# RelayBypass.net
KiCad netlist of a schematic drawn in Altium Designer
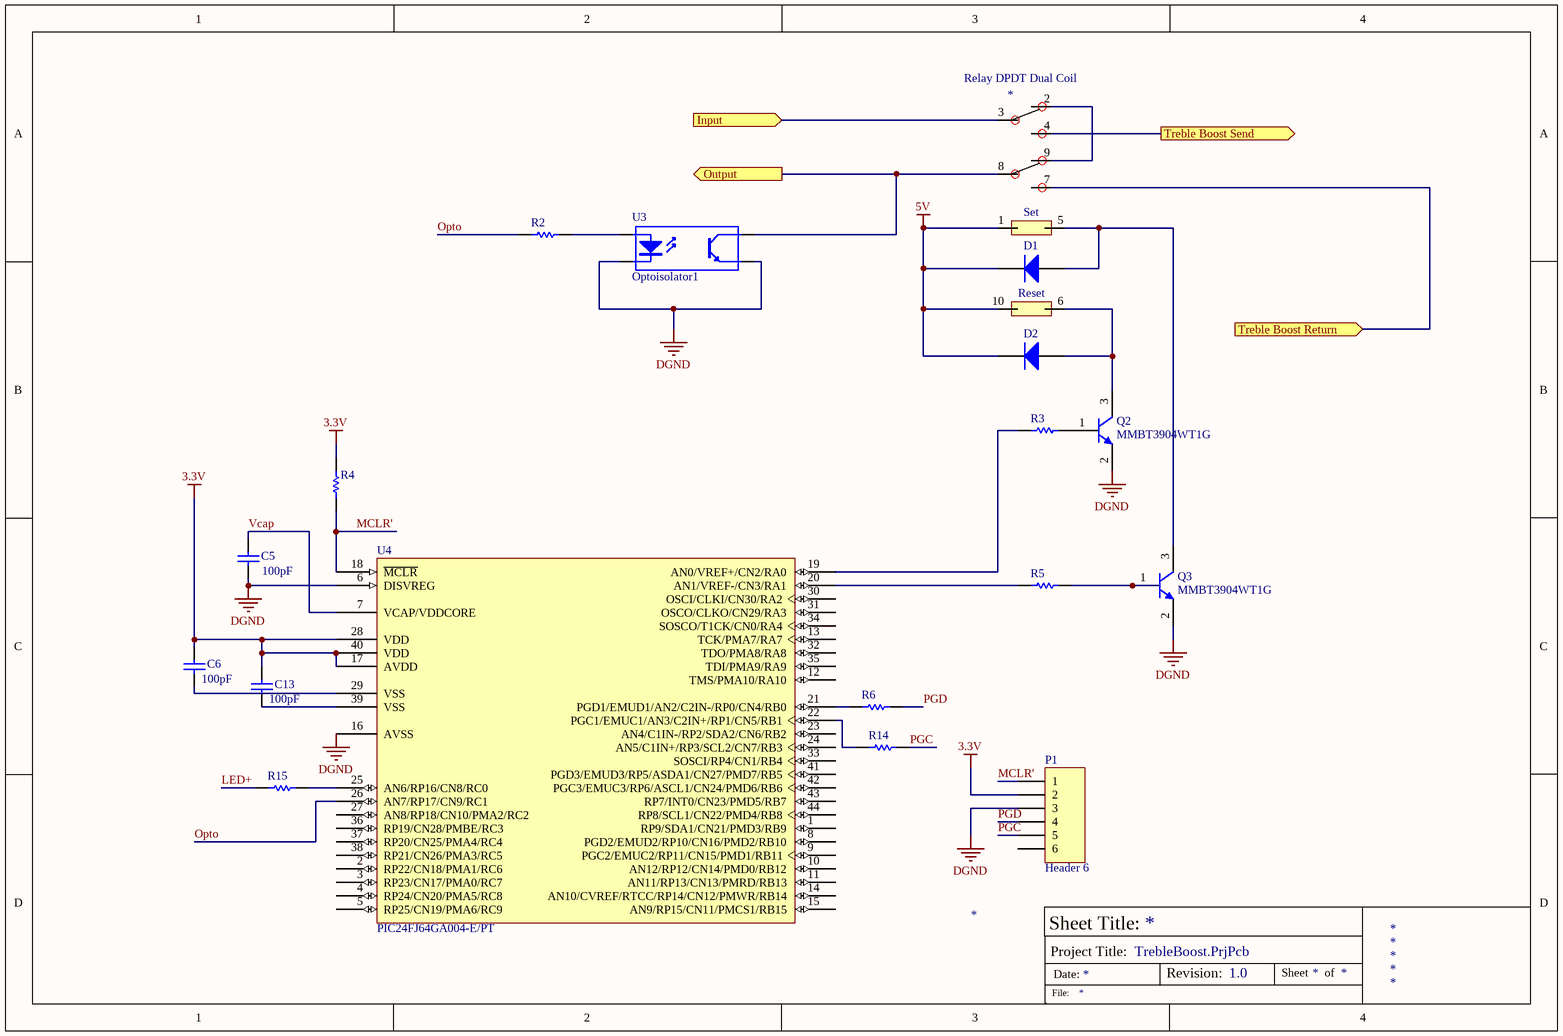
[diagram p0: RelayBypass.SchDoc]

(export (version "E")
  (design (tool "Eeschema 10.0.6"))
  (components
    (comp (ref "*")
      (value "Relay DPDT Dual Coil")
      (footprint "EB2 Relay")
      (libsource (lib "Parts") (part "Relay DPDT Dual Coil"))
    )
    (comp (ref "C5")
      (value "100pF")
      (footprint "1210")
      (description "Ceramic Chip Capacitor - Standard")
      (fields (field (name "Comment") "C1210") (field (name "PUBLISHER") "Altium Limited"))
      (libsource (lib "KEMET Chip Capacitor") (part "C1210"))
    )
    (comp (ref "C6")
      (value "100pF")
      (footprint "1206")
      (description "Ceramic Chip Capacitor - Standard")
      (fields (field (name "Comment") "C1206") (field (name "PUBLISHER") "Altium Limited"))
      (libsource (lib "KEMET Chip Capacitor") (part "C1206"))
    )
    (comp (ref "C13")
      (value "100pF")
      (footprint "1206")
      (description "Ceramic Chip Capacitor - Standard")
      (fields (field (name "Comment") "C1206") (field (name "PUBLISHER") "Altium Limited"))
      (libsource (lib "KEMET Chip Capacitor") (part "C1206"))
    )
    (comp (ref "D1")
      (value "Diode 1N4148")
      (footprint "DO-35")
      (description "High Conductance Fast Diode")
      (fields (field (name "PUBLISHER") "Altium Limited"))
      (libsource (lib "Miscellaneous Devices") (part "Diode 1N4148"))
    )
    (comp (ref "D2")
      (value "Diode 1N4148")
      (footprint "DO-35")
      (description "High Conductance Fast Diode")
      (fields (field (name "PUBLISHER") "Altium Limited"))
      (libsource (lib "Miscellaneous Devices") (part "Diode 1N4148"))
    )
    (comp (ref "P1")
      (value "Header 6")
      (footprint "HDR1X6")
      (description "Header, 6-Pin")
      (fields (field (name "PUBLISHER") "Altium Limited"))
      (libsource (lib "Miscellaneous Connectors") (part "Header 6"))
    )
    (comp (ref "Q2")
      (value "MMBT3904WT1G")
      (footprint "ONSC-SC-70-3-419-04_V")
      (description "General Purpose Transistor, NPN Silicon, 3-Pin SC70, Pb-Free, Tape and Reel")
      (fields (field (name "MANUFACTURER") "On Semiconductor"))
      (libsource (lib "ON Semi General Purpose Transistors") (part "MMBT3904WT1G"))
    )
    (comp (ref "Q3")
      (value "MMBT3904WT1G")
      (footprint "ONSC-SC-70-3-419-04_V")
      (description "General Purpose Transistor, NPN Silicon, 3-Pin SC70, Pb-Free, Tape and Reel")
      (fields (field (name "MANUFACTURER") "On Semiconductor"))
      (libsource (lib "ON Semi General Purpose Transistors") (part "MMBT3904WT1G"))
    )
    (comp (ref "R2")
      (value "ERJ6BQ")
      (footprint "6-0805")
      (fields (field (name "PUBLISHER") "Altium Limited"))
      (libsource (lib "Panasonic Resistor") (part "ERJ6BQ"))
    )
    (comp (ref "R3")
      (value "ERJ6BQ")
      (footprint "6-0805")
      (fields (field (name "PUBLISHER") "Altium Limited"))
      (libsource (lib "Panasonic Resistor") (part "ERJ6BQ"))
    )
    (comp (ref "R4")
      (value "ERJ6BQ")
      (footprint "6-0805")
      (fields (field (name "PUBLISHER") "Altium Limited"))
      (libsource (lib "Panasonic Resistor") (part "ERJ6BQ"))
    )
    (comp (ref "R5")
      (value "ERJ6BQ")
      (footprint "6-0805")
      (fields (field (name "PUBLISHER") "Altium Limited"))
      (libsource (lib "Panasonic Resistor") (part "ERJ6BQ"))
    )
    (comp (ref "R6")
      (value "ERJ6BQ")
      (footprint "6-0805")
      (fields (field (name "PUBLISHER") "Altium Limited"))
      (libsource (lib "Panasonic Resistor") (part "ERJ6BQ"))
    )
    (comp (ref "R14")
      (value "ERJ6BQ")
      (footprint "6-0805")
      (fields (field (name "PUBLISHER") "Altium Limited"))
      (libsource (lib "Panasonic Resistor") (part "ERJ6BQ"))
    )
    (comp (ref "R15")
      (value "ERJ6BQ")
      (footprint "6-0805")
      (fields (field (name "PUBLISHER") "Altium Limited"))
      (libsource (lib "Panasonic Resistor") (part "ERJ6BQ"))
    )
    (comp (ref "U3")
      (value "Optoisolator1")
      (footprint "DIP-4")
      (description "4-Pin Phototransistor Optocoupler")
      (fields (field (name "PUBLISHER") "Altium Limited"))
      (libsource (lib "Miscellaneous Devices") (part "Optoisolator1"))
    )
    (comp (ref "U4")
      (value "PIC24FJ64GA004-E/PT")
      (footprint "TQFP-PT44_N")
      (fields (field (name "PUBLISHER") "Altium Limited"))
      (libsource (lib "Microchip Microcontroller 16-Bit PIC24F") (part "PIC24FJ64GA004-E/PT"))
    )
  )
  (nets
    (net (code "1") (name "/Input") (class "Default")
      (node (ref "*") (pin "3") (pinfunction "3_3") (pintype "passive"))
    )
    (net (code "2") (name "/LED+") (class "Default")
      (node (ref "R15") (pin "2") (pinfunction "2_2") (pintype "passive"))
    )
    (net (code "3") (name "/MCLR'") (class "Default")
      (node (ref "P1") (pin "1") (pinfunction "1_1") (pintype "passive"))
      (node (ref "R4") (pin "1") (pinfunction "1_1") (pintype "passive"))
      (node (ref "U4") (pin "18") (pinfunction "~{MCLR}_18") (pintype "input"))
    )
    (net (code "4") (name "/Opto") (class "Default")
      (node (ref "R2") (pin "2") (pinfunction "2_2") (pintype "passive"))
      (node (ref "U4") (pin "26") (pinfunction "AN7/RP17/CN9/RC1_26") (pintype "bidirectional"))
    )
    (net (code "5") (name "/Output") (class "Default")
      (node (ref "*") (pin "8") (pinfunction "8_8") (pintype "passive"))
      (node (ref "U3") (pin "4") (pinfunction "C_4") (pintype "passive"))
    )
    (net (code "6") (name "/PGC") (class "Default")
      (node (ref "P1") (pin "5") (pinfunction "5_5") (pintype "passive"))
      (node (ref "R14") (pin "1") (pinfunction "1_1") (pintype "passive"))
    )
    (net (code "7") (name "/PGD") (class "Default")
      (node (ref "P1") (pin "4") (pinfunction "4_4") (pintype "passive"))
      (node (ref "R6") (pin "1") (pinfunction "1_1") (pintype "passive"))
    )
    (net (code "8") (name "/Treble Boost Return") (class "Default")
      (node (ref "*") (pin "7") (pinfunction "7_7") (pintype "passive"))
    )
    (net (code "9") (name "/Treble Boost Send") (class "Default")
      (node (ref "*") (pin "4") (pinfunction "4_4") (pintype "passive"))
    )
    (net (code "10") (name "/Vcap") (class "Default")
      (node (ref "C5") (pin "2") (pinfunction "2_2") (pintype "passive"))
      (node (ref "U4") (pin "7") (pinfunction "VCAP/VDDCORE_7") (pintype "power_in"))
    )
    (net (code "11") (name "3.3V") (class "Default")
      (node (ref "C13") (pin "2") (pinfunction "2_2") (pintype "passive"))
      (node (ref "C6") (pin "2") (pinfunction "2_2") (pintype "passive"))
      (node (ref "P1") (pin "2") (pinfunction "2_2") (pintype "passive"))
      (node (ref "R4") (pin "2") (pinfunction "2_2") (pintype "passive"))
      (node (ref "U4") (pin "17") (pinfunction "AVDD_17") (pintype "power_in"))
      (node (ref "U4") (pin "28") (pinfunction "VDD_28") (pintype "power_in"))
      (node (ref "U4") (pin "40") (pinfunction "VDD_40") (pintype "power_in"))
    )
    (net (code "12") (name "5V") (class "Default")
      (node (ref "*") (pin "1") (pinfunction "1_1") (pintype "passive"))
      (node (ref "*") (pin "10") (pinfunction "10_10") (pintype "passive"))
      (node (ref "D1") (pin "2") (pinfunction "K_2") (pintype "passive"))
      (node (ref "D2") (pin "2") (pinfunction "K_2") (pintype "passive"))
    )
    (net (code "13") (name "DGND") (class "Default")
      (node (ref "C5") (pin "1") (pinfunction "1_1") (pintype "passive"))
      (node (ref "P1") (pin "3") (pinfunction "3_3") (pintype "passive"))
      (node (ref "Q2") (pin "2") (pinfunction "E_2") (pintype "passive"))
      (node (ref "Q3") (pin "2") (pinfunction "E_2") (pintype "passive"))
      (node (ref "U3") (pin "2") (pinfunction "K_2") (pintype "passive"))
      (node (ref "U3") (pin "3") (pinfunction "E_3") (pintype "passive"))
      (node (ref "U4") (pin "16") (pinfunction "AVSS_16") (pintype "power_in"))
      (node (ref "U4") (pin "6") (pinfunction "DISVREG_6") (pintype "input"))
    )
    (net (code "14") (name "Net-(*-Pad2)") (class "Default")
      (node (ref "*") (pin "2") (pinfunction "2_2") (pintype "passive"))
      (node (ref "*") (pin "9") (pinfunction "9_9") (pintype "passive"))
    )
    (net (code "15") (name "Net-(C6-Pad1)") (class "Default")
      (node (ref "C6") (pin "1") (pinfunction "1_1") (pintype "passive"))
      (node (ref "U4") (pin "29") (pinfunction "VSS_29") (pintype "power_in"))
    )
    (net (code "16") (name "Net-(C13-Pad1)") (class "Default")
      (node (ref "C13") (pin "1") (pinfunction "1_1") (pintype "passive"))
      (node (ref "U4") (pin "39") (pinfunction "VSS_39") (pintype "power_in"))
    )
    (net (code "17") (name "Net-(D1-A)") (class "Default")
      (node (ref "*") (pin "5") (pinfunction "5_5") (pintype "passive"))
      (node (ref "D1") (pin "1") (pinfunction "A_1") (pintype "passive"))
      (node (ref "Q3") (pin "3") (pinfunction "C_3") (pintype "passive"))
    )
    (net (code "18") (name "Net-(D2-A)") (class "Default")
      (node (ref "*") (pin "6") (pinfunction "6_6") (pintype "passive"))
      (node (ref "D2") (pin "1") (pinfunction "A_1") (pintype "passive"))
      (node (ref "Q2") (pin "3") (pinfunction "C_3") (pintype "passive"))
    )
    (net (code "19") (name "Net-(Q2-B)") (class "Default")
      (node (ref "Q2") (pin "1") (pinfunction "B_1") (pintype "passive"))
      (node (ref "R3") (pin "1") (pinfunction "1_1") (pintype "passive"))
    )
    (net (code "20") (name "Net-(Q3-B)") (class "Default")
      (node (ref "Q3") (pin "1") (pinfunction "B_1") (pintype "passive"))
      (node (ref "R5") (pin "1") (pinfunction "1_1") (pintype "passive"))
    )
    (net (code "21") (name "Net-(U3-A)") (class "Default")
      (node (ref "R2") (pin "1") (pinfunction "1_1") (pintype "passive"))
      (node (ref "U3") (pin "1") (pinfunction "A_1") (pintype "passive"))
    )
    (net (code "22") (name "Net-(U4-AN0{slash}VREF+{slash}CN2{slash}RA0)") (class "Default")
      (node (ref "R3") (pin "2") (pinfunction "2_2") (pintype "passive"))
      (node (ref "U4") (pin "19") (pinfunction "AN0/VREF+/CN2/RA0_19") (pintype "bidirectional"))
    )
    (net (code "23") (name "Net-(U4-AN1{slash}VREF-{slash}CN3{slash}RA1)") (class "Default")
      (node (ref "R5") (pin "2") (pinfunction "2_2") (pintype "passive"))
      (node (ref "U4") (pin "20") (pinfunction "AN1/VREF-/CN3/RA1_20") (pintype "bidirectional"))
    )
    (net (code "24") (name "Net-(U4-AN6{slash}RP16{slash}CN8{slash}RC0)") (class "Default")
      (node (ref "R15") (pin "1") (pinfunction "1_1") (pintype "passive"))
      (node (ref "U4") (pin "25") (pinfunction "AN6/RP16/CN8/RC0_25") (pintype "bidirectional"))
    )
    (net (code "25") (name "Net-(U4-PGC1{slash}EMUC1{slash}AN3{slash}C2IN+{slash}RP1{slash}CN5{slash}RB1)") (class "Default")
      (node (ref "R14") (pin "2") (pinfunction "2_2") (pintype "passive"))
      (node (ref "U4") (pin "22") (pinfunction "PGC1/EMUC1/AN3/C2IN+/RP1/CN5/RB1_22") (pintype "bidirectional"))
    )
    (net (code "26") (name "Net-(U4-PGD1{slash}EMUD1{slash}AN2{slash}C2IN-{slash}RP0{slash}CN4{slash}RB0)") (class "Default")
      (node (ref "R6") (pin "2") (pinfunction "2_2") (pintype "passive"))
      (node (ref "U4") (pin "21") (pinfunction "PGD1/EMUD1/AN2/C2IN-/RP0/CN4/RB0_21") (pintype "bidirectional"))
    )
    (net (code "27") (name "unconnected-(P1-Pad6)") (class "Default")
      (node (ref "P1") (pin "6") (pinfunction "6_6") (pintype "passive"))
    )
    (net (code "28") (name "unconnected-(U4-AN4{slash}C1IN-{slash}RP2{slash}SDA2{slash}CN6{slash}RB2-Pad23)") (class "Default")
      (node (ref "U4") (pin "23") (pinfunction "AN4/C1IN-/RP2/SDA2/CN6/RB2_23") (pintype "bidirectional"))
    )
    (net (code "29") (name "unconnected-(U4-AN5{slash}C1IN+{slash}RP3{slash}SCL2{slash}CN7{slash}RB3-Pad24)") (class "Default")
      (node (ref "U4") (pin "24") (pinfunction "AN5/C1IN+/RP3/SCL2/CN7/RB3_24") (pintype "bidirectional"))
    )
    (net (code "30") (name "unconnected-(U4-AN8{slash}RP18{slash}CN10{slash}PMA2{slash}RC2-Pad27)") (class "Default")
      (node (ref "U4") (pin "27") (pinfunction "AN8/RP18/CN10/PMA2/RC2_27") (pintype "bidirectional"))
    )
    (net (code "31") (name "unconnected-(U4-AN9{slash}RP15{slash}CN11{slash}PMCS1{slash}RB15-Pad15)") (class "Default")
      (node (ref "U4") (pin "15") (pinfunction "AN9/RP15/CN11/PMCS1/RB15_15") (pintype "bidirectional"))
    )
    (net (code "32") (name "unconnected-(U4-AN10{slash}CVREF{slash}RTCC{slash}RP14{slash}CN12{slash}PMWR{slash}RB14-Pad14)") (class "Default")
      (node (ref "U4") (pin "14") (pinfunction "AN10/CVREF/RTCC/RP14/CN12/PMWR/RB14_14") (pintype "bidirectional"))
    )
    (net (code "33") (name "unconnected-(U4-AN11{slash}RP13{slash}CN13{slash}PMRD{slash}RB13-Pad11)") (class "Default")
      (node (ref "U4") (pin "11") (pinfunction "AN11/RP13/CN13/PMRD/RB13_11") (pintype "bidirectional"))
    )
    (net (code "34") (name "unconnected-(U4-AN12{slash}RP12{slash}CN14{slash}PMD0{slash}RB12-Pad10)") (class "Default")
      (node (ref "U4") (pin "10") (pinfunction "AN12/RP12/CN14/PMD0/RB12_10") (pintype "bidirectional"))
    )
    (net (code "35") (name "unconnected-(U4-OSCI{slash}CLKI{slash}CN30{slash}RA2-Pad30)") (class "Default")
      (node (ref "U4") (pin "30") (pinfunction "OSCI/CLKI/CN30/RA2_30") (pintype "bidirectional"))
    )
    (net (code "36") (name "unconnected-(U4-OSCO{slash}CLKO{slash}CN29{slash}RA3-Pad31)") (class "Default")
      (node (ref "U4") (pin "31") (pinfunction "OSCO/CLKO/CN29/RA3_31") (pintype "bidirectional"))
    )
    (net (code "37") (name "unconnected-(U4-PGC2{slash}EMUC2{slash}RP11{slash}CN15{slash}PMD1{slash}RB11-Pad9)") (class "Default")
      (node (ref "U4") (pin "9") (pinfunction "PGC2/EMUC2/RP11/CN15/PMD1/RB11_9") (pintype "bidirectional"))
    )
    (net (code "38") (name "unconnected-(U4-PGC3{slash}EMUC3{slash}RP6{slash}ASCL1{slash}CN24{slash}PMD6{slash}RB6-Pad42)") (class "Default")
      (node (ref "U4") (pin "42") (pinfunction "PGC3/EMUC3/RP6/ASCL1/CN24/PMD6/RB6_42") (pintype "bidirectional"))
    )
    (net (code "39") (name "unconnected-(U4-PGD2{slash}EMUD2{slash}RP10{slash}CN16{slash}PMD2{slash}RB10-Pad8)") (class "Default")
      (node (ref "U4") (pin "8") (pinfunction "PGD2/EMUD2/RP10/CN16/PMD2/RB10_8") (pintype "bidirectional"))
    )
    (net (code "40") (name "unconnected-(U4-PGD3{slash}EMUD3{slash}RP5{slash}ASDA1{slash}CN27{slash}PMD7{slash}RB5-Pad41)") (class "Default")
      (node (ref "U4") (pin "41") (pinfunction "PGD3/EMUD3/RP5/ASDA1/CN27/PMD7/RB5_41") (pintype "bidirectional"))
    )
    (net (code "41") (name "unconnected-(U4-RP7{slash}INT0{slash}CN23{slash}PMD5{slash}RB7-Pad43)") (class "Default")
      (node (ref "U4") (pin "43") (pinfunction "RP7/INT0/CN23/PMD5/RB7_43") (pintype "bidirectional"))
    )
    (net (code "42") (name "unconnected-(U4-RP8{slash}SCL1{slash}CN22{slash}PMD4{slash}RB8-Pad44)") (class "Default")
      (node (ref "U4") (pin "44") (pinfunction "RP8/SCL1/CN22/PMD4/RB8_44") (pintype "bidirectional"))
    )
    (net (code "43") (name "unconnected-(U4-RP9{slash}SDA1{slash}CN21{slash}PMD3{slash}RB9-Pad1)") (class "Default")
      (node (ref "U4") (pin "1") (pinfunction "RP9/SDA1/CN21/PMD3/RB9_1") (pintype "bidirectional"))
    )
    (net (code "44") (name "unconnected-(U4-RP19{slash}CN28{slash}PMBE{slash}RC3-Pad36)") (class "Default")
      (node (ref "U4") (pin "36") (pinfunction "RP19/CN28/PMBE/RC3_36") (pintype "bidirectional"))
    )
    (net (code "45") (name "unconnected-(U4-RP20{slash}CN25{slash}PMA4{slash}RC4-Pad37)") (class "Default")
      (node (ref "U4") (pin "37") (pinfunction "RP20/CN25/PMA4/RC4_37") (pintype "bidirectional"))
    )
    (net (code "46") (name "unconnected-(U4-RP21{slash}CN26{slash}PMA3{slash}RC5-Pad38)") (class "Default")
      (node (ref "U4") (pin "38") (pinfunction "RP21/CN26/PMA3/RC5_38") (pintype "bidirectional"))
    )
    (net (code "47") (name "unconnected-(U4-RP22{slash}CN18{slash}PMA1{slash}RC6-Pad2)") (class "Default")
      (node (ref "U4") (pin "2") (pinfunction "RP22/CN18/PMA1/RC6_2") (pintype "bidirectional"))
    )
    (net (code "48") (name "unconnected-(U4-RP23{slash}CN17{slash}PMA0{slash}RC7-Pad3)") (class "Default")
      (node (ref "U4") (pin "3") (pinfunction "RP23/CN17/PMA0/RC7_3") (pintype "bidirectional"))
    )
    (net (code "49") (name "unconnected-(U4-RP24{slash}CN20{slash}PMA5{slash}RC8-Pad4)") (class "Default")
      (node (ref "U4") (pin "4") (pinfunction "RP24/CN20/PMA5/RC8_4") (pintype "bidirectional"))
    )
    (net (code "50") (name "unconnected-(U4-RP25{slash}CN19{slash}PMA6{slash}RC9-Pad5)") (class "Default")
      (node (ref "U4") (pin "5") (pinfunction "RP25/CN19/PMA6/RC9_5") (pintype "bidirectional"))
    )
    (net (code "51") (name "unconnected-(U4-SOSCI{slash}RP4{slash}CN1{slash}RB4-Pad33)") (class "Default")
      (node (ref "U4") (pin "33") (pinfunction "SOSCI/RP4/CN1/RB4_33") (pintype "bidirectional"))
    )
    (net (code "52") (name "unconnected-(U4-SOSCO{slash}T1CK{slash}CN0{slash}RA4-Pad34)") (class "Default")
      (node (ref "U4") (pin "34") (pinfunction "SOSCO/T1CK/CN0/RA4_34") (pintype "bidirectional"))
    )
    (net (code "53") (name "unconnected-(U4-TCK{slash}PMA7{slash}RA7-Pad13)") (class "Default")
      (node (ref "U4") (pin "13") (pinfunction "TCK/PMA7/RA7_13") (pintype "bidirectional"))
    )
    (net (code "54") (name "unconnected-(U4-TDI{slash}PMA9{slash}RA9-Pad35)") (class "Default")
      (node (ref "U4") (pin "35") (pinfunction "TDI/PMA9/RA9_35") (pintype "bidirectional"))
    )
    (net (code "55") (name "unconnected-(U4-TDO{slash}PMA8{slash}RA8-Pad32)") (class "Default")
      (node (ref "U4") (pin "32") (pinfunction "TDO/PMA8/RA8_32") (pintype "bidirectional"))
    )
    (net (code "56") (name "unconnected-(U4-TMS{slash}PMA10{slash}RA10-Pad12)") (class "Default")
      (node (ref "U4") (pin "12") (pinfunction "TMS/PMA10/RA10_12") (pintype "bidirectional"))
    )
  )
)
